# Secondary_protection.net
KiCad netlist of a schematic drawn in Altium Designer
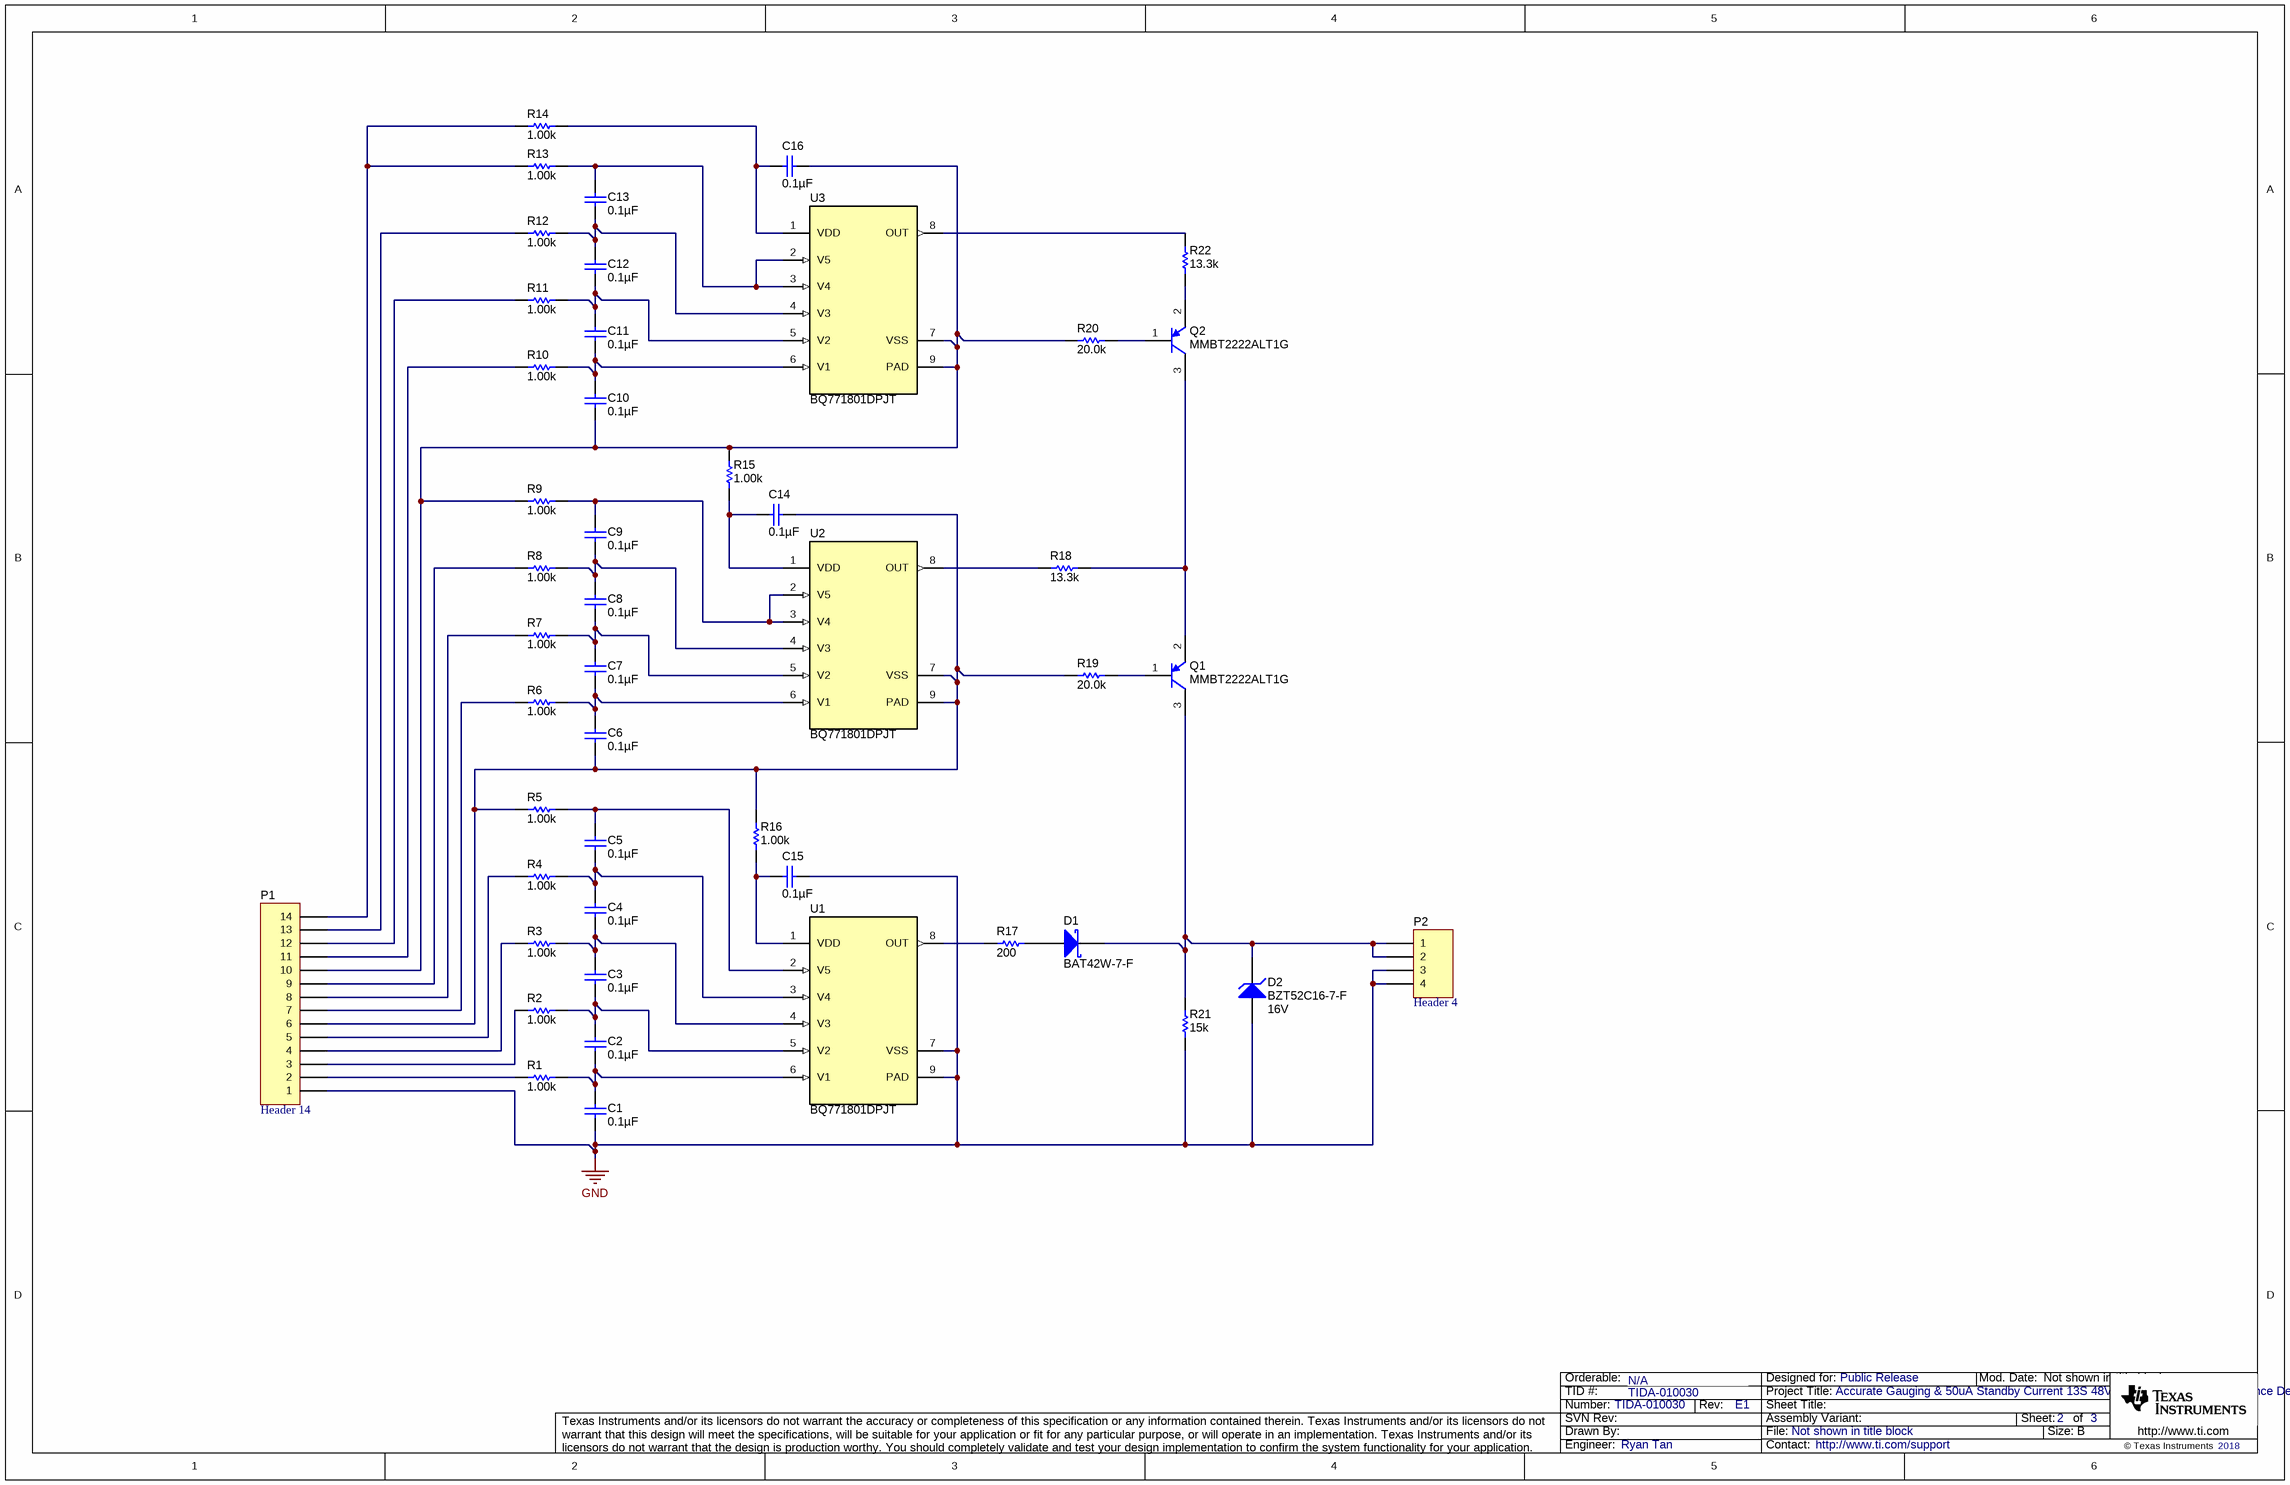
[diagram p0: Secondary protection.SchDoc]

(export (version "E")
  (design (tool "Eeschema 10.0.6"))
  (components
    (comp (ref "C1")
      (value "GRM188R71H104KA93D")
      (footprint "0603")
      (description "CAP, CERM, 0.1 µF, 50 V,+/- 10%, X7R, 0603")
      (fields
        (field (name "VALUEDISPLAYED") "0.1µF")
        (field (name "MANUFACTURER") "MuRata")
        (field (name "PUBLISHER") "Texas Instruments")
      )
      (libsource (lib "Capacitor_Ceramic") (part "GRM188R71H104KA93D"))
    )
    (comp (ref "C2")
      (value "GRM188R71H104KA93D")
      (footprint "0603")
      (description "CAP, CERM, 0.1 µF, 50 V,+/- 10%, X7R, 0603")
      (fields
        (field (name "VALUEDISPLAYED") "0.1µF")
        (field (name "MANUFACTURER") "MuRata")
        (field (name "PUBLISHER") "Texas Instruments")
      )
      (libsource (lib "Capacitor_Ceramic") (part "GRM188R71H104KA93D"))
    )
    (comp (ref "C3")
      (value "GRM188R71H104KA93D")
      (footprint "0603")
      (description "CAP, CERM, 0.1 µF, 50 V,+/- 10%, X7R, 0603")
      (fields
        (field (name "VALUEDISPLAYED") "0.1µF")
        (field (name "MANUFACTURER") "MuRata")
        (field (name "PUBLISHER") "Texas Instruments")
      )
      (libsource (lib "Capacitor_Ceramic") (part "GRM188R71H104KA93D"))
    )
    (comp (ref "C4")
      (value "GRM188R71H104KA93D")
      (footprint "0603")
      (description "CAP, CERM, 0.1 µF, 50 V,+/- 10%, X7R, 0603")
      (fields
        (field (name "VALUEDISPLAYED") "0.1µF")
        (field (name "MANUFACTURER") "MuRata")
        (field (name "PUBLISHER") "Texas Instruments")
      )
      (libsource (lib "Capacitor_Ceramic") (part "GRM188R71H104KA93D"))
    )
    (comp (ref "C5")
      (value "GRM188R71H104KA93D")
      (footprint "0603")
      (description "CAP, CERM, 0.1 µF, 50 V,+/- 10%, X7R, 0603")
      (fields
        (field (name "VALUEDISPLAYED") "0.1µF")
        (field (name "MANUFACTURER") "MuRata")
        (field (name "PUBLISHER") "Texas Instruments")
      )
      (libsource (lib "Capacitor_Ceramic") (part "GRM188R71H104KA93D"))
    )
    (comp (ref "C6")
      (value "GRM188R71H104KA93D")
      (footprint "0603")
      (description "CAP, CERM, 0.1 µF, 50 V,+/- 10%, X7R, 0603")
      (fields
        (field (name "VALUEDISPLAYED") "0.1µF")
        (field (name "MANUFACTURER") "MuRata")
        (field (name "PUBLISHER") "Texas Instruments")
      )
      (libsource (lib "Capacitor_Ceramic") (part "GRM188R71H104KA93D"))
    )
    (comp (ref "C7")
      (value "GRM188R71H104KA93D")
      (footprint "0603")
      (description "CAP, CERM, 0.1 µF, 50 V,+/- 10%, X7R, 0603")
      (fields
        (field (name "VALUEDISPLAYED") "0.1µF")
        (field (name "MANUFACTURER") "MuRata")
        (field (name "PUBLISHER") "Texas Instruments")
      )
      (libsource (lib "Capacitor_Ceramic") (part "GRM188R71H104KA93D"))
    )
    (comp (ref "C8")
      (value "GRM188R71H104KA93D")
      (footprint "0603")
      (description "CAP, CERM, 0.1 µF, 50 V,+/- 10%, X7R, 0603")
      (fields
        (field (name "VALUEDISPLAYED") "0.1µF")
        (field (name "MANUFACTURER") "MuRata")
        (field (name "PUBLISHER") "Texas Instruments")
      )
      (libsource (lib "Capacitor_Ceramic") (part "GRM188R71H104KA93D"))
    )
    (comp (ref "C9")
      (value "GRM188R71H104KA93D")
      (footprint "0603")
      (description "CAP, CERM, 0.1 µF, 50 V,+/- 10%, X7R, 0603")
      (fields
        (field (name "VALUEDISPLAYED") "0.1µF")
        (field (name "MANUFACTURER") "MuRata")
        (field (name "PUBLISHER") "Texas Instruments")
      )
      (libsource (lib "Capacitor_Ceramic") (part "GRM188R71H104KA93D"))
    )
    (comp (ref "C10")
      (value "GRM188R71H104KA93D")
      (footprint "0603")
      (description "CAP, CERM, 0.1 µF, 50 V,+/- 10%, X7R, 0603")
      (fields
        (field (name "VALUEDISPLAYED") "0.1µF")
        (field (name "MANUFACTURER") "MuRata")
        (field (name "PUBLISHER") "Texas Instruments")
      )
      (libsource (lib "Capacitor_Ceramic") (part "GRM188R71H104KA93D"))
    )
    (comp (ref "C11")
      (value "GRM188R71H104KA93D")
      (footprint "0603")
      (description "CAP, CERM, 0.1 µF, 50 V,+/- 10%, X7R, 0603")
      (fields
        (field (name "VALUEDISPLAYED") "0.1µF")
        (field (name "MANUFACTURER") "MuRata")
        (field (name "PUBLISHER") "Texas Instruments")
      )
      (libsource (lib "Capacitor_Ceramic") (part "GRM188R71H104KA93D"))
    )
    (comp (ref "C12")
      (value "GRM188R71H104KA93D")
      (footprint "0603")
      (description "CAP, CERM, 0.1 µF, 50 V,+/- 10%, X7R, 0603")
      (fields
        (field (name "VALUEDISPLAYED") "0.1µF")
        (field (name "MANUFACTURER") "MuRata")
        (field (name "PUBLISHER") "Texas Instruments")
      )
      (libsource (lib "Capacitor_Ceramic") (part "GRM188R71H104KA93D"))
    )
    (comp (ref "C13")
      (value "GRM188R71H104KA93D")
      (footprint "0603")
      (description "CAP, CERM, 0.1 µF, 50 V,+/- 10%, X7R, 0603")
      (fields
        (field (name "VALUEDISPLAYED") "0.1µF")
        (field (name "MANUFACTURER") "MuRata")
        (field (name "PUBLISHER") "Texas Instruments")
      )
      (libsource (lib "Capacitor_Ceramic") (part "GRM188R71H104KA93D"))
    )
    (comp (ref "C14")
      (value "GRM188R71H104KA93D")
      (footprint "0603")
      (description "CAP, CERM, 0.1 µF, 50 V,+/- 10%, X7R, 0603")
      (fields
        (field (name "VALUEDISPLAYED") "0.1µF")
        (field (name "MANUFACTURER") "MuRata")
        (field (name "PUBLISHER") "Texas Instruments")
      )
      (libsource (lib "Capacitor_Ceramic") (part "GRM188R71H104KA93D"))
    )
    (comp (ref "C15")
      (value "GRM188R71H104KA93D")
      (footprint "0603")
      (description "CAP, CERM, 0.1 µF, 50 V,+/- 10%, X7R, 0603")
      (fields
        (field (name "VALUEDISPLAYED") "0.1µF")
        (field (name "MANUFACTURER") "MuRata")
        (field (name "PUBLISHER") "Texas Instruments")
      )
      (libsource (lib "Capacitor_Ceramic") (part "GRM188R71H104KA93D"))
    )
    (comp (ref "C16")
      (value "GRM188R71H104KA93D")
      (footprint "0603")
      (description "CAP, CERM, 0.1 µF, 50 V,+/- 10%, X7R, 0603")
      (fields
        (field (name "VALUEDISPLAYED") "0.1µF")
        (field (name "MANUFACTURER") "MuRata")
        (field (name "PUBLISHER") "Texas Instruments")
      )
      (libsource (lib "Capacitor_Ceramic") (part "GRM188R71H104KA93D"))
    )
    (comp (ref "D1")
      (value "BAT42W-7-F")
      (footprint "SOD-123")
      (description "Diode, Schottky, 30 V, 0.2 A, SOD-123")
      (fields (field (name "MANUFACTURER") "Diodes Inc.") (field (name "PUBLISHER") "Texas Instruments"))
      (libsource (lib "Diode") (part "BAT42W-7-F"))
    )
    (comp (ref "D2")
      (value "BZT52C16-7-F")
      (footprint "SOD-123")
      (description "Diode, Zener, 16 V, 500 mW, AEC-Q101, SOD-123")
      (fields
        (field (name "ALTIUM_VALUE") "16V")
        (field (name "MANUFACTURER") "Diodes Inc.")
        (field (name "SYMBOLCREATOR") "a0412235")
        (field (name "PUBLISHER") "Texas Instruments")
      )
      (libsource (lib "ZenerDiodes") (part "BZT52C16-7-F"))
    )
    (comp (ref "P1")
      (value "Header 14")
      (footprint "HDR1X14")
      (description "Header, 14-Pin")
      (fields (field (name "PUBLISHER") "Altium Limited"))
      (libsource (lib "Miscellaneous Connectors") (part "Header 14"))
    )
    (comp (ref "P2")
      (value "Header 4")
      (footprint "HDR1X4")
      (description "Header, 4-Pin")
      (fields (field (name "PUBLISHER") "Altium Limited"))
      (libsource (lib "Miscellaneous Connectors") (part "Header 4"))
    )
    (comp (ref "Q1")
      (value "MMBT2222ALT1G")
      (footprint "SOT-23")
      (description "Transistor, PNP, 40 V, 0.6 A, SOT-23")
      (fields (field (name "MANUFACTURER") "Diodes Inc.") (field (name "PUBLISHER") "Texas Instruments"))
      (libsource (lib "Bipolar_Transistor") (part "MMBT3906-7-F, Diodes Inc."))
    )
    (comp (ref "Q2")
      (value "MMBT2222ALT1G")
      (footprint "SOT-23")
      (description "Transistor, PNP, 40 V, 0.6 A, SOT-23")
      (fields (field (name "MANUFACTURER") "Diodes Inc.") (field (name "PUBLISHER") "Texas Instruments"))
      (libsource (lib "Bipolar_Transistor") (part "MMBT3906-7-F, Diodes Inc."))
    )
    (comp (ref "R1")
      (value "CRCW06031K00FKEA")
      (footprint "0603")
      (description "RES, 1.00 k, 1%, 0.1 W, 0603")
      (fields
        (field (name "VALUEDISPLAYED") "1.00k")
        (field (name "MANUFACTURER") "Vishay-Dale")
        (field (name "PUBLISHER") "Texas Instruments")
      )
      (libsource (lib "Resistor_0603") (part "CRCW06031K00FKEA"))
    )
    (comp (ref "R2")
      (value "CRCW06031K00FKEA")
      (footprint "0603")
      (description "RES, 1.00 k, 1%, 0.1 W, 0603")
      (fields
        (field (name "VALUEDISPLAYED") "1.00k")
        (field (name "MANUFACTURER") "Vishay-Dale")
        (field (name "PUBLISHER") "Texas Instruments")
      )
      (libsource (lib "Resistor_0603") (part "CRCW06031K00FKEA"))
    )
    (comp (ref "R3")
      (value "CRCW06031K00FKEA")
      (footprint "0603")
      (description "RES, 1.00 k, 1%, 0.1 W, 0603")
      (fields
        (field (name "VALUEDISPLAYED") "1.00k")
        (field (name "MANUFACTURER") "Vishay-Dale")
        (field (name "PUBLISHER") "Texas Instruments")
      )
      (libsource (lib "Resistor_0603") (part "CRCW06031K00FKEA"))
    )
    (comp (ref "R4")
      (value "CRCW06031K00FKEA")
      (footprint "0603")
      (description "RES, 1.00 k, 1%, 0.1 W, 0603")
      (fields
        (field (name "VALUEDISPLAYED") "1.00k")
        (field (name "MANUFACTURER") "Vishay-Dale")
        (field (name "PUBLISHER") "Texas Instruments")
      )
      (libsource (lib "Resistor_0603") (part "CRCW06031K00FKEA"))
    )
    (comp (ref "R5")
      (value "CRCW06031K00FKEA")
      (footprint "0603")
      (description "RES, 1.00 k, 1%, 0.1 W, 0603")
      (fields
        (field (name "VALUEDISPLAYED") "1.00k")
        (field (name "MANUFACTURER") "Vishay-Dale")
        (field (name "PUBLISHER") "Texas Instruments")
      )
      (libsource (lib "Resistor_0603") (part "CRCW06031K00FKEA"))
    )
    (comp (ref "R6")
      (value "CRCW06031K00FKEA")
      (footprint "0603")
      (description "RES, 1.00 k, 1%, 0.1 W, 0603")
      (fields
        (field (name "VALUEDISPLAYED") "1.00k")
        (field (name "MANUFACTURER") "Vishay-Dale")
        (field (name "PUBLISHER") "Texas Instruments")
      )
      (libsource (lib "Resistor_0603") (part "CRCW06031K00FKEA"))
    )
    (comp (ref "R7")
      (value "CRCW06031K00FKEA")
      (footprint "0603")
      (description "RES, 1.00 k, 1%, 0.1 W, 0603")
      (fields
        (field (name "VALUEDISPLAYED") "1.00k")
        (field (name "MANUFACTURER") "Vishay-Dale")
        (field (name "PUBLISHER") "Texas Instruments")
      )
      (libsource (lib "Resistor_0603") (part "CRCW06031K00FKEA"))
    )
    (comp (ref "R8")
      (value "CRCW06031K00FKEA")
      (footprint "0603")
      (description "RES, 1.00 k, 1%, 0.1 W, 0603")
      (fields
        (field (name "VALUEDISPLAYED") "1.00k")
        (field (name "MANUFACTURER") "Vishay-Dale")
        (field (name "PUBLISHER") "Texas Instruments")
      )
      (libsource (lib "Resistor_0603") (part "CRCW06031K00FKEA"))
    )
    (comp (ref "R9")
      (value "CRCW06031K00FKEA")
      (footprint "0603")
      (description "RES, 1.00 k, 1%, 0.1 W, 0603")
      (fields
        (field (name "VALUEDISPLAYED") "1.00k")
        (field (name "MANUFACTURER") "Vishay-Dale")
        (field (name "PUBLISHER") "Texas Instruments")
      )
      (libsource (lib "Resistor_0603") (part "CRCW06031K00FKEA"))
    )
    (comp (ref "R10")
      (value "CRCW06031K00FKEA")
      (footprint "0603")
      (description "RES, 1.00 k, 1%, 0.1 W, 0603")
      (fields
        (field (name "VALUEDISPLAYED") "1.00k")
        (field (name "MANUFACTURER") "Vishay-Dale")
        (field (name "PUBLISHER") "Texas Instruments")
      )
      (libsource (lib "Resistor_0603") (part "CRCW06031K00FKEA"))
    )
    (comp (ref "R11")
      (value "CRCW06031K00FKEA")
      (footprint "0603")
      (description "RES, 1.00 k, 1%, 0.1 W, 0603")
      (fields
        (field (name "VALUEDISPLAYED") "1.00k")
        (field (name "MANUFACTURER") "Vishay-Dale")
        (field (name "PUBLISHER") "Texas Instruments")
      )
      (libsource (lib "Resistor_0603") (part "CRCW06031K00FKEA"))
    )
    (comp (ref "R12")
      (value "CRCW06031K00FKEA")
      (footprint "0603")
      (description "RES, 1.00 k, 1%, 0.1 W, 0603")
      (fields
        (field (name "VALUEDISPLAYED") "1.00k")
        (field (name "MANUFACTURER") "Vishay-Dale")
        (field (name "PUBLISHER") "Texas Instruments")
      )
      (libsource (lib "Resistor_0603") (part "CRCW06031K00FKEA"))
    )
    (comp (ref "R13")
      (value "CRCW06031K00FKEA")
      (footprint "0603")
      (description "RES, 1.00 k, 1%, 0.1 W, 0603")
      (fields
        (field (name "VALUEDISPLAYED") "1.00k")
        (field (name "MANUFACTURER") "Vishay-Dale")
        (field (name "PUBLISHER") "Texas Instruments")
      )
      (libsource (lib "Resistor_0603") (part "CRCW06031K00FKEA"))
    )
    (comp (ref "R14")
      (value "CRCW06031K00FKEA")
      (footprint "0603")
      (description "RES, 1.00 k, 1%, 0.1 W, 0603")
      (fields
        (field (name "VALUEDISPLAYED") "1.00k")
        (field (name "MANUFACTURER") "Vishay-Dale")
        (field (name "PUBLISHER") "Texas Instruments")
      )
      (libsource (lib "Resistor_0603") (part "CRCW06031K00FKEA"))
    )
    (comp (ref "R15")
      (value "CRCW06031K00FKEA")
      (footprint "0603")
      (description "RES, 1.00 k, 1%, 0.1 W, 0603")
      (fields
        (field (name "VALUEDISPLAYED") "1.00k")
        (field (name "MANUFACTURER") "Vishay-Dale")
        (field (name "PUBLISHER") "Texas Instruments")
      )
      (libsource (lib "Resistor_0603") (part "CRCW06031K00FKEA"))
    )
    (comp (ref "R16")
      (value "CRCW06031K00FKEA")
      (footprint "0603")
      (description "RES, 1.00 k, 1%, 0.1 W, 0603")
      (fields
        (field (name "VALUEDISPLAYED") "1.00k")
        (field (name "MANUFACTURER") "Vishay-Dale")
        (field (name "PUBLISHER") "Texas Instruments")
      )
      (libsource (lib "Resistor_0603") (part "CRCW06031K00FKEA"))
    )
    (comp (ref "R17")
      (value "CRCW0603200RJNEA")
      (footprint "0603")
      (description "RES, 200, 5%, 0.1 W, 0603")
      (fields
        (field (name "VALUEDISPLAYED") "200")
        (field (name "MANUFACTURER") "Vishay-Dale")
        (field (name "PUBLISHER") "Texas Instruments")
      )
      (libsource (lib "Resistor_0603") (part "CRCW0603200RJNEA"))
    )
    (comp (ref "R18")
      (value "CRCW060313K3FKEA")
      (footprint "0603")
      (description "RES, 13.3 k, 1%, 0.1 W, 0603")
      (fields
        (field (name "VALUEDISPLAYED") "13.3k")
        (field (name "MANUFACTURER") "Vishay-Dale")
        (field (name "PUBLISHER") "Texas Instruments")
      )
      (libsource (lib "Resistor_0603") (part "CRCW060313K3FKEA"))
    )
    (comp (ref "R19")
      (value "CRCW060320K0FKEA")
      (footprint "0603")
      (description "RES, 20.0 k, 1%, 0.1 W, 0603")
      (fields
        (field (name "VALUEDISPLAYED") "20.0k")
        (field (name "MANUFACTURER") "Vishay-Dale")
        (field (name "PUBLISHER") "Texas Instruments")
      )
      (libsource (lib "Resistor_0603") (part "CRCW060320K0FKEA"))
    )
    (comp (ref "R20")
      (value "CRCW060320K0FKEA")
      (footprint "0603")
      (description "RES, 20.0 k, 1%, 0.1 W, 0603")
      (fields
        (field (name "VALUEDISPLAYED") "20.0k")
        (field (name "MANUFACTURER") "Vishay-Dale")
        (field (name "PUBLISHER") "Texas Instruments")
      )
      (libsource (lib "Resistor_0603") (part "CRCW060320K0FKEA"))
    )
    (comp (ref "R21")
      (value "CRCW060315K0JNEA")
      (footprint "0603")
      (description "RES, 15 k, 5%, 0.1 W, 0603")
      (fields
        (field (name "VALUEDISPLAYED") "15k")
        (field (name "MANUFACTURER") "Vishay-Dale")
        (field (name "PUBLISHER") "Texas Instruments")
      )
      (libsource (lib "Resistor_0603") (part "CRCW060315K0JNEA"))
    )
    (comp (ref "R22")
      (value "CRCW060313K3FKEA")
      (footprint "0603")
      (description "RES, 13.3 k, 1%, 0.1 W, 0603")
      (fields
        (field (name "VALUEDISPLAYED") "13.3k")
        (field (name "MANUFACTURER") "Vishay-Dale")
        (field (name "PUBLISHER") "Texas Instruments")
      )
      (libsource (lib "Resistor_0603") (part "CRCW060313K3FKEA"))
    )
    (comp (ref "U1")
      (value "BQ771801DPJT")
      (footprint "DPJ0008A")
      (description "Family 2-5S Overvoltage Protector with Internal Delay Timer, DPJ0008A (WSON-8)")
      (fields
        (field (name "ALTERNATE PARTNUMBER") "BQ771801DPJR")
        (field (name "MANUFACTURER") "Texas Instruments")
        (field (name "PARTNUMBER") "BQ771801DPJT")
      )
      (libsource (lib "Altium Vault - TI") (part "CMP-0078897-2"))
    )
    (comp (ref "U2")
      (value "BQ771801DPJT")
      (footprint "DPJ0008A")
      (description "Family 2-5S Overvoltage Protector with Internal Delay Timer, DPJ0008A (WSON-8)")
      (fields
        (field (name "ALTERNATE PARTNUMBER") "BQ771801DPJR")
        (field (name "MANUFACTURER") "Texas Instruments")
        (field (name "PARTNUMBER") "BQ771801DPJT")
      )
      (libsource (lib "Altium Vault - TI") (part "CMP-0078897-2"))
    )
    (comp (ref "U3")
      (value "BQ771801DPJT")
      (footprint "DPJ0008A")
      (description "Family 2-5S Overvoltage Protector with Internal Delay Timer, DPJ0008A (WSON-8)")
      (fields
        (field (name "ALTERNATE PARTNUMBER") "BQ771801DPJR")
        (field (name "MANUFACTURER") "Texas Instruments")
        (field (name "PARTNUMBER") "BQ771801DPJT")
      )
      (libsource (lib "Altium Vault - TI") (part "CMP-0078897-2"))
    )
  )
  (nets
    (net (code "1") (name "GND") (class "Default")
      (node (ref "C1") (pin "2") (pinfunction "2_2") (pintype "passive"))
      (node (ref "C15") (pin "2") (pinfunction "2_2") (pintype "passive"))
      (node (ref "D2") (pin "2") (pinfunction "A_2") (pintype "passive"))
      (node (ref "P1") (pin "1") (pinfunction "1_1") (pintype "passive"))
      (node (ref "P2") (pin "3") (pinfunction "3_3") (pintype "passive"))
      (node (ref "P2") (pin "4") (pinfunction "4_4") (pintype "passive"))
      (node (ref "R21") (pin "2") (pinfunction "2_2") (pintype "passive"))
      (node (ref "U1") (pin "7") (pinfunction "VSS_7") (pintype "power_in"))
      (node (ref "U1") (pin "9") (pinfunction "PAD_9") (pintype "passive"))
    )
    (net (code "2") (name "Net-(D1-A)") (class "Default")
      (node (ref "D1") (pin "2") (pinfunction "A_2") (pintype "passive"))
      (node (ref "R17") (pin "2") (pinfunction "2_2") (pintype "passive"))
    )
    (net (code "3") (name "Net-(D1-K)") (class "Default")
      (node (ref "D1") (pin "1") (pinfunction "K_1") (pintype "passive"))
      (node (ref "D2") (pin "1") (pinfunction "K_1") (pintype "passive"))
      (node (ref "P2") (pin "1") (pinfunction "1_1") (pintype "passive"))
      (node (ref "P2") (pin "2") (pinfunction "2_2") (pintype "passive"))
      (node (ref "Q1") (pin "3") (pinfunction "C_3") (pintype "passive"))
      (node (ref "R21") (pin "1") (pinfunction "1_1") (pintype "passive"))
    )
    (net (code "4") (name "Net-(P1-Pad2)") (class "Default")
      (node (ref "P1") (pin "2") (pinfunction "2_2") (pintype "passive"))
      (node (ref "R1") (pin "2") (pinfunction "2_2") (pintype "passive"))
    )
    (net (code "5") (name "Net-(P1-Pad3)") (class "Default")
      (node (ref "P1") (pin "3") (pinfunction "3_3") (pintype "passive"))
      (node (ref "R2") (pin "2") (pinfunction "2_2") (pintype "passive"))
    )
    (net (code "6") (name "Net-(P1-Pad4)") (class "Default")
      (node (ref "P1") (pin "4") (pinfunction "4_4") (pintype "passive"))
      (node (ref "R3") (pin "2") (pinfunction "2_2") (pintype "passive"))
    )
    (net (code "7") (name "Net-(P1-Pad5)") (class "Default")
      (node (ref "P1") (pin "5") (pinfunction "5_5") (pintype "passive"))
      (node (ref "R4") (pin "2") (pinfunction "2_2") (pintype "passive"))
    )
    (net (code "8") (name "Net-(P1-Pad7)") (class "Default")
      (node (ref "P1") (pin "7") (pinfunction "7_7") (pintype "passive"))
      (node (ref "R6") (pin "2") (pinfunction "2_2") (pintype "passive"))
    )
    (net (code "9") (name "Net-(P1-Pad8)") (class "Default")
      (node (ref "P1") (pin "8") (pinfunction "8_8") (pintype "passive"))
      (node (ref "R7") (pin "2") (pinfunction "2_2") (pintype "passive"))
    )
    (net (code "10") (name "Net-(P1-Pad9)") (class "Default")
      (node (ref "P1") (pin "9") (pinfunction "9_9") (pintype "passive"))
      (node (ref "R8") (pin "2") (pinfunction "2_2") (pintype "passive"))
    )
    (net (code "11") (name "Net-(P1-Pad11)") (class "Default")
      (node (ref "P1") (pin "11") (pinfunction "11_11") (pintype "passive"))
      (node (ref "R10") (pin "2") (pinfunction "2_2") (pintype "passive"))
    )
    (net (code "12") (name "Net-(P1-Pad12)") (class "Default")
      (node (ref "P1") (pin "12") (pinfunction "12_12") (pintype "passive"))
      (node (ref "R11") (pin "2") (pinfunction "2_2") (pintype "passive"))
    )
    (net (code "13") (name "Net-(P1-Pad13)") (class "Default")
      (node (ref "P1") (pin "13") (pinfunction "13_13") (pintype "passive"))
      (node (ref "R12") (pin "2") (pinfunction "2_2") (pintype "passive"))
    )
    (net (code "14") (name "Net-(P1-Pad14)") (class "Default")
      (node (ref "P1") (pin "14") (pinfunction "14_14") (pintype "passive"))
      (node (ref "R13") (pin "2") (pinfunction "2_2") (pintype "passive"))
      (node (ref "R14") (pin "2") (pinfunction "2_2") (pintype "passive"))
    )
    (net (code "15") (name "Net-(Q1-B)") (class "Default")
      (node (ref "Q1") (pin "1") (pinfunction "B_1") (pintype "passive"))
      (node (ref "R19") (pin "2") (pinfunction "2_2") (pintype "passive"))
    )
    (net (code "16") (name "Net-(Q1-E)") (class "Default")
      (node (ref "Q1") (pin "2") (pinfunction "E_2") (pintype "passive"))
      (node (ref "Q2") (pin "3") (pinfunction "C_3") (pintype "passive"))
      (node (ref "R18") (pin "2") (pinfunction "2_2") (pintype "passive"))
    )
    (net (code "17") (name "Net-(Q2-B)") (class "Default")
      (node (ref "Q2") (pin "1") (pinfunction "B_1") (pintype "passive"))
      (node (ref "R20") (pin "2") (pinfunction "2_2") (pintype "passive"))
    )
    (net (code "18") (name "Net-(Q2-E)") (class "Default")
      (node (ref "Q2") (pin "2") (pinfunction "E_2") (pintype "passive"))
      (node (ref "R22") (pin "2") (pinfunction "2_2") (pintype "passive"))
    )
    (net (code "19") (name "Net-(U1-OUT)") (class "Default")
      (node (ref "R17") (pin "1") (pinfunction "1_1") (pintype "passive"))
      (node (ref "U1") (pin "8") (pinfunction "OUT_8") (pintype "output"))
    )
    (net (code "20") (name "Net-(U1-V1)") (class "Default")
      (node (ref "C1") (pin "1") (pinfunction "1_1") (pintype "passive"))
      (node (ref "C2") (pin "2") (pinfunction "2_2") (pintype "passive"))
      (node (ref "R1") (pin "1") (pinfunction "1_1") (pintype "passive"))
      (node (ref "U1") (pin "6") (pinfunction "V1_6") (pintype "input"))
    )
    (net (code "21") (name "Net-(U1-V2)") (class "Default")
      (node (ref "C2") (pin "1") (pinfunction "1_1") (pintype "passive"))
      (node (ref "C3") (pin "2") (pinfunction "2_2") (pintype "passive"))
      (node (ref "R2") (pin "1") (pinfunction "1_1") (pintype "passive"))
      (node (ref "U1") (pin "5") (pinfunction "V2_5") (pintype "input"))
    )
    (net (code "22") (name "Net-(U1-V3)") (class "Default")
      (node (ref "C3") (pin "1") (pinfunction "1_1") (pintype "passive"))
      (node (ref "C4") (pin "2") (pinfunction "2_2") (pintype "passive"))
      (node (ref "R3") (pin "1") (pinfunction "1_1") (pintype "passive"))
      (node (ref "U1") (pin "4") (pinfunction "V3_4") (pintype "input"))
    )
    (net (code "23") (name "Net-(U1-V4)") (class "Default")
      (node (ref "C4") (pin "1") (pinfunction "1_1") (pintype "passive"))
      (node (ref "C5") (pin "2") (pinfunction "2_2") (pintype "passive"))
      (node (ref "R4") (pin "1") (pinfunction "1_1") (pintype "passive"))
      (node (ref "U1") (pin "3") (pinfunction "V4_3") (pintype "input"))
    )
    (net (code "24") (name "Net-(U1-V5)") (class "Default")
      (node (ref "C5") (pin "1") (pinfunction "1_1") (pintype "passive"))
      (node (ref "R5") (pin "1") (pinfunction "1_1") (pintype "passive"))
      (node (ref "U1") (pin "2") (pinfunction "V5_2") (pintype "input"))
    )
    (net (code "25") (name "Net-(U1-VDD)") (class "Default")
      (node (ref "C15") (pin "1") (pinfunction "1_1") (pintype "passive"))
      (node (ref "R16") (pin "2") (pinfunction "2_2") (pintype "passive"))
      (node (ref "U1") (pin "1") (pinfunction "VDD_1") (pintype "power_in"))
    )
    (net (code "26") (name "Net-(U2-OUT)") (class "Default")
      (node (ref "R18") (pin "1") (pinfunction "1_1") (pintype "passive"))
      (node (ref "U2") (pin "8") (pinfunction "OUT_8") (pintype "output"))
    )
    (net (code "27") (name "Net-(U2-PAD)") (class "Default")
      (node (ref "C14") (pin "2") (pinfunction "2_2") (pintype "passive"))
      (node (ref "C6") (pin "2") (pinfunction "2_2") (pintype "passive"))
      (node (ref "P1") (pin "6") (pinfunction "6_6") (pintype "passive"))
      (node (ref "R16") (pin "1") (pinfunction "1_1") (pintype "passive"))
      (node (ref "R19") (pin "1") (pinfunction "1_1") (pintype "passive"))
      (node (ref "R5") (pin "2") (pinfunction "2_2") (pintype "passive"))
      (node (ref "U2") (pin "7") (pinfunction "VSS_7") (pintype "power_in"))
      (node (ref "U2") (pin "9") (pinfunction "PAD_9") (pintype "passive"))
    )
    (net (code "28") (name "Net-(U2-V1)") (class "Default")
      (node (ref "C6") (pin "1") (pinfunction "1_1") (pintype "passive"))
      (node (ref "C7") (pin "2") (pinfunction "2_2") (pintype "passive"))
      (node (ref "R6") (pin "1") (pinfunction "1_1") (pintype "passive"))
      (node (ref "U2") (pin "6") (pinfunction "V1_6") (pintype "input"))
    )
    (net (code "29") (name "Net-(U2-V2)") (class "Default")
      (node (ref "C7") (pin "1") (pinfunction "1_1") (pintype "passive"))
      (node (ref "C8") (pin "2") (pinfunction "2_2") (pintype "passive"))
      (node (ref "R7") (pin "1") (pinfunction "1_1") (pintype "passive"))
      (node (ref "U2") (pin "5") (pinfunction "V2_5") (pintype "input"))
    )
    (net (code "30") (name "Net-(U2-V3)") (class "Default")
      (node (ref "C8") (pin "1") (pinfunction "1_1") (pintype "passive"))
      (node (ref "C9") (pin "2") (pinfunction "2_2") (pintype "passive"))
      (node (ref "R8") (pin "1") (pinfunction "1_1") (pintype "passive"))
      (node (ref "U2") (pin "4") (pinfunction "V3_4") (pintype "input"))
    )
    (net (code "31") (name "Net-(U2-V4)") (class "Default")
      (node (ref "C9") (pin "1") (pinfunction "1_1") (pintype "passive"))
      (node (ref "R9") (pin "1") (pinfunction "1_1") (pintype "passive"))
      (node (ref "U2") (pin "2") (pinfunction "V5_2") (pintype "input"))
      (node (ref "U2") (pin "3") (pinfunction "V4_3") (pintype "input"))
    )
    (net (code "32") (name "Net-(U2-VDD)") (class "Default")
      (node (ref "C14") (pin "1") (pinfunction "1_1") (pintype "passive"))
      (node (ref "R15") (pin "2") (pinfunction "2_2") (pintype "passive"))
      (node (ref "U2") (pin "1") (pinfunction "VDD_1") (pintype "power_in"))
    )
    (net (code "33") (name "Net-(U3-OUT)") (class "Default")
      (node (ref "R22") (pin "1") (pinfunction "1_1") (pintype "passive"))
      (node (ref "U3") (pin "8") (pinfunction "OUT_8") (pintype "output"))
    )
    (net (code "34") (name "Net-(U3-PAD)") (class "Default")
      (node (ref "C10") (pin "2") (pinfunction "2_2") (pintype "passive"))
      (node (ref "C16") (pin "2") (pinfunction "2_2") (pintype "passive"))
      (node (ref "P1") (pin "10") (pinfunction "10_10") (pintype "passive"))
      (node (ref "R15") (pin "1") (pinfunction "1_1") (pintype "passive"))
      (node (ref "R20") (pin "1") (pinfunction "1_1") (pintype "passive"))
      (node (ref "R9") (pin "2") (pinfunction "2_2") (pintype "passive"))
      (node (ref "U3") (pin "7") (pinfunction "VSS_7") (pintype "power_in"))
      (node (ref "U3") (pin "9") (pinfunction "PAD_9") (pintype "passive"))
    )
    (net (code "35") (name "Net-(U3-V1)") (class "Default")
      (node (ref "C10") (pin "1") (pinfunction "1_1") (pintype "passive"))
      (node (ref "C11") (pin "2") (pinfunction "2_2") (pintype "passive"))
      (node (ref "R10") (pin "1") (pinfunction "1_1") (pintype "passive"))
      (node (ref "U3") (pin "6") (pinfunction "V1_6") (pintype "input"))
    )
    (net (code "36") (name "Net-(U3-V2)") (class "Default")
      (node (ref "C11") (pin "1") (pinfunction "1_1") (pintype "passive"))
      (node (ref "C12") (pin "2") (pinfunction "2_2") (pintype "passive"))
      (node (ref "R11") (pin "1") (pinfunction "1_1") (pintype "passive"))
      (node (ref "U3") (pin "5") (pinfunction "V2_5") (pintype "input"))
    )
    (net (code "37") (name "Net-(U3-V3)") (class "Default")
      (node (ref "C12") (pin "1") (pinfunction "1_1") (pintype "passive"))
      (node (ref "C13") (pin "2") (pinfunction "2_2") (pintype "passive"))
      (node (ref "R12") (pin "1") (pinfunction "1_1") (pintype "passive"))
      (node (ref "U3") (pin "4") (pinfunction "V3_4") (pintype "input"))
    )
    (net (code "38") (name "Net-(U3-V4)") (class "Default")
      (node (ref "C13") (pin "1") (pinfunction "1_1") (pintype "passive"))
      (node (ref "R13") (pin "1") (pinfunction "1_1") (pintype "passive"))
      (node (ref "U3") (pin "2") (pinfunction "V5_2") (pintype "input"))
      (node (ref "U3") (pin "3") (pinfunction "V4_3") (pintype "input"))
    )
    (net (code "39") (name "Net-(U3-VDD)") (class "Default")
      (node (ref "C16") (pin "1") (pinfunction "1_1") (pintype "passive"))
      (node (ref "R14") (pin "1") (pinfunction "1_1") (pintype "passive"))
      (node (ref "U3") (pin "1") (pinfunction "VDD_1") (pintype "power_in"))
    )
  )
)
